# EEPROM.net
KiCad netlist of a schematic drawn in Altium Designer
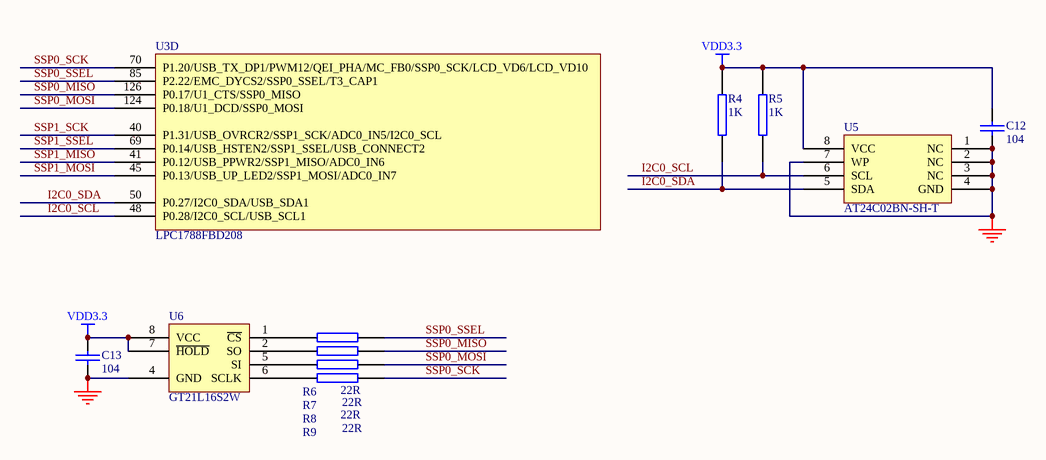
[diagram p0: EEPROM.SchDoc]

(export (version "E")
  (design (tool "Eeschema 10.0.6"))
  (components
    (comp (ref "C12")
      (value "104")
      (footprint "C0603")
      (description "Capacitor")
      (libsource (lib "*") (part "CAP"))
    )
    (comp (ref "C13")
      (value "104")
      (footprint "C0603")
      (description "Capacitor")
      (libsource (lib "*") (part "CAP"))
    )
    (comp (ref "R4") (value "1K") (footprint "R0603") (libsource (lib "*") (part "RES2")))
    (comp (ref "R5") (value "1K") (footprint "R0603") (libsource (lib "*") (part "RES2")))
    (comp (ref "R6") (value "22R") (footprint "R0603") (libsource (lib "*") (part "RES2")))
    (comp (ref "R7") (value "22R") (footprint "R0603") (libsource (lib "*") (part "RES2")))
    (comp (ref "R8") (value "22R") (footprint "R0603") (libsource (lib "*") (part "RES2")))
    (comp (ref "R9") (value "22R") (footprint "R0603") (libsource (lib "*") (part "RES2")))
    (comp (ref "U3")
      (value "LPC1788FBD208")
      (footprint "QFP208")
      (libsource (lib "LPC1788") (part "LPC1788FBD208"))
    )
    (comp (ref "U5") (value "AT24C02BN-SH-T") (footprint "SOP8") (libsource (lib "*") (part "AT24C02")))
    (comp (ref "U6") (value "GT21L16S2W") (footprint "SOP8") (libsource (lib "*") (part "GT21L16T1W")))
  )
  (nets
    (net (code "1") (name "/I2C0_SCL") (class "Default")
      (node (ref "R5") (pin "1") (pinfunction "1_1") (pintype "passive"))
      (node (ref "U3") (pin "48") (pinfunction "P0.28/I2C0_SCL/USB_SCL1_48") (pintype "passive"))
      (node (ref "U5") (pin "6") (pinfunction "SCL_6") (pintype "passive"))
    )
    (net (code "2") (name "/I2C0_SDA") (class "Default")
      (node (ref "R4") (pin "1") (pinfunction "1_1") (pintype "passive"))
      (node (ref "U3") (pin "50") (pinfunction "P0.27/I2C0_SDA/USB_SDA1_50") (pintype "passive"))
      (node (ref "U5") (pin "5") (pinfunction "SDA_5") (pintype "passive"))
    )
    (net (code "3") (name "/SSP0_MISO") (class "Default")
      (node (ref "R7") (pin "2") (pinfunction "2_2") (pintype "passive"))
      (node (ref "U3") (pin "126") (pinfunction "P0.17/U1_CTS/SSP0_MISO_126") (pintype "passive"))
    )
    (net (code "4") (name "/SSP0_MOSI") (class "Default")
      (node (ref "R8") (pin "2") (pinfunction "2_2") (pintype "passive"))
      (node (ref "U3") (pin "124") (pinfunction "P0.18/U1_DCD/SSP0_MOSI_124") (pintype "passive"))
    )
    (net (code "5") (name "/SSP0_SCK") (class "Default")
      (node (ref "R9") (pin "2") (pinfunction "2_2") (pintype "passive"))
      (node (ref "U3") (pin "70") (pinfunction "P1.20/USB_TX_DP1/PWM12/QEI_PHA/MC_FB0/SSP0_SCK/LCD_VD6/LCD_VD10_70") (pintype "passive"))
    )
    (net (code "6") (name "/SSP0_SSEL") (class "Default")
      (node (ref "R6") (pin "2") (pinfunction "2_2") (pintype "passive"))
      (node (ref "U3") (pin "85") (pinfunction "P2.22/EMC_DYCS2/SSP0_SSEL/T3_CAP1_85") (pintype "passive"))
    )
    (net (code "7") (name "/SSP1_MISO") (class "Default")
      (node (ref "U3") (pin "41") (pinfunction "P0.12/USB_PPWR2/SSP1_MISO/ADC0_IN6_41") (pintype "passive"))
    )
    (net (code "8") (name "/SSP1_MOSI") (class "Default")
      (node (ref "U3") (pin "45") (pinfunction "P0.13/USB_UP_LED2/SSP1_MOSI/ADC0_IN7_45") (pintype "passive"))
    )
    (net (code "9") (name "/SSP1_SCK") (class "Default")
      (node (ref "U3") (pin "40") (pinfunction "P1.31/USB_OVRCR2/SSP1_SCK/ADC0_IN5/I2C0_SCL_40") (pintype "passive"))
    )
    (net (code "10") (name "/SSP1_SSEL") (class "Default")
      (node (ref "U3") (pin "69") (pinfunction "P0.14/USB_HSTEN2/SSP1_SSEL/USB_CONNECT2_69") (pintype "passive"))
    )
    (net (code "11") (name "GND") (class "Default")
      (node (ref "C12") (pin "2") (pinfunction "2_2") (pintype "passive"))
      (node (ref "C13") (pin "2") (pinfunction "2_2") (pintype "passive"))
      (node (ref "U5") (pin "1") (pinfunction "NC_1") (pintype "passive"))
      (node (ref "U5") (pin "2") (pinfunction "NC_2") (pintype "passive"))
      (node (ref "U5") (pin "3") (pinfunction "NC_3") (pintype "passive"))
      (node (ref "U5") (pin "4") (pinfunction "GND_4") (pintype "passive"))
      (node (ref "U5") (pin "7") (pinfunction "WP_7") (pintype "passive"))
      (node (ref "U6") (pin "4") (pinfunction "GND_4") (pintype "passive"))
    )
    (net (code "12") (name "NC") (class "Default")
      (node (ref "U6") (pin "3") (pinfunction "NC_3") (pintype "passive"))
    )
    (net (code "13") (name "Net-(U6-SCLK)") (class "Default")
      (node (ref "R9") (pin "1") (pinfunction "1_1") (pintype "passive"))
      (node (ref "U6") (pin "6") (pinfunction "SCLK_6") (pintype "passive"))
    )
    (net (code "14") (name "Net-(U6-SI)") (class "Default")
      (node (ref "R8") (pin "1") (pinfunction "1_1") (pintype "passive"))
      (node (ref "U6") (pin "5") (pinfunction "SI_5") (pintype "passive"))
    )
    (net (code "15") (name "Net-(U6-SO)") (class "Default")
      (node (ref "R7") (pin "1") (pinfunction "1_1") (pintype "passive"))
      (node (ref "U6") (pin "2") (pinfunction "SO_2") (pintype "passive"))
    )
    (net (code "16") (name "Net-(U6-~{CS})") (class "Default")
      (node (ref "R6") (pin "1") (pinfunction "1_1") (pintype "passive"))
      (node (ref "U6") (pin "1") (pinfunction "~{CS}_1") (pintype "passive"))
    )
    (net (code "17") (name "VDD3.3") (class "Default")
      (node (ref "C12") (pin "1") (pinfunction "1_1") (pintype "passive"))
      (node (ref "C13") (pin "1") (pinfunction "1_1") (pintype "passive"))
      (node (ref "R4") (pin "2") (pinfunction "2_2") (pintype "passive"))
      (node (ref "R5") (pin "2") (pinfunction "2_2") (pintype "passive"))
      (node (ref "U5") (pin "8") (pinfunction "VCC_8") (pintype "passive"))
      (node (ref "U6") (pin "7") (pinfunction "~{HOLD}_7") (pintype "passive"))
      (node (ref "U6") (pin "8") (pinfunction "VCC_8") (pintype "passive"))
    )
  )
)
